# P1.net
KiCad netlist of a schematic drawn in Altium Designer
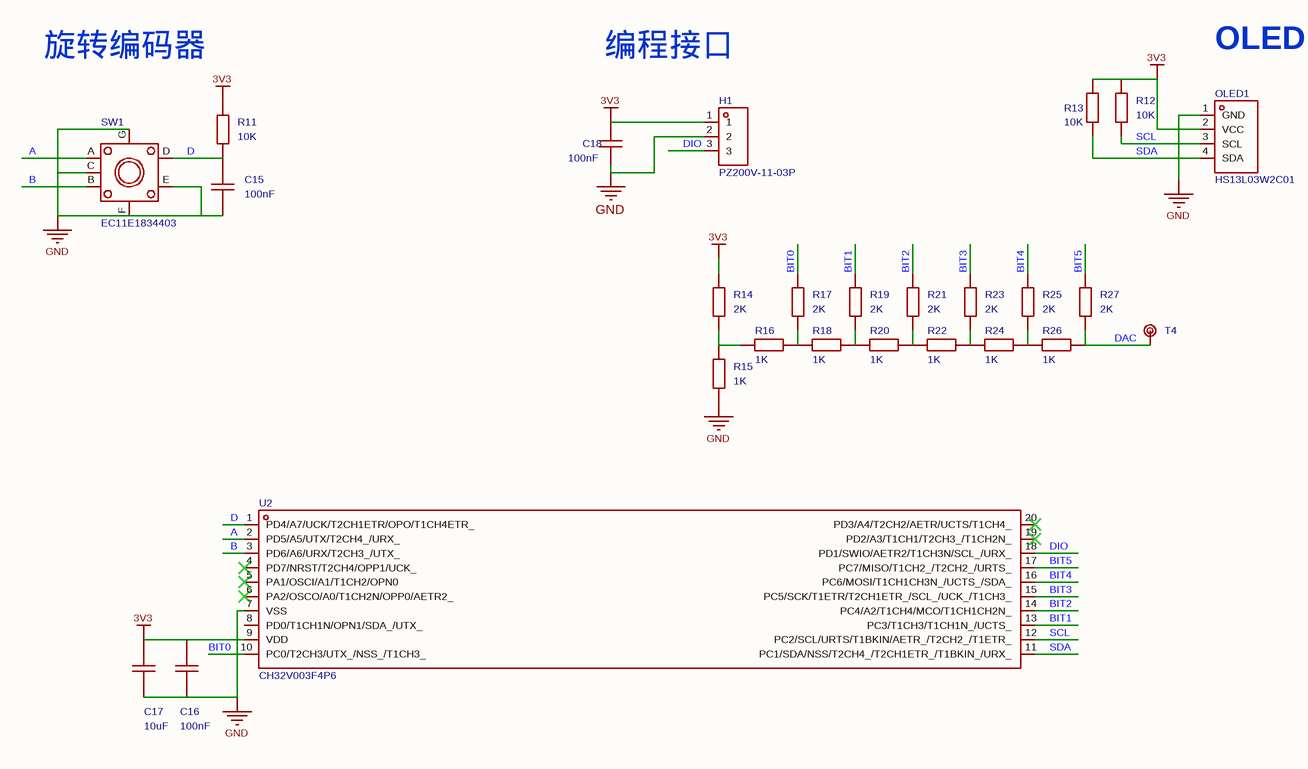
[diagram p0: P1.schdoc]

(export (version "E")
  (design (tool "Eeschema 10.0.6"))
  (components
    (comp (ref "C15")
      (value "100nF")
      (footprint "C0603")
      (libsource (lib "altium-import") (part "root_1_CAP_0603_"))
    )
    (comp (ref "C16")
      (value "100nF")
      (footprint "C0603")
      (libsource (lib "altium-import") (part "root_1_CAP_0603_"))
    )
    (comp (ref "C17")
      (value "10uF")
      (footprint "C0603")
      (libsource (lib "altium-import") (part "root_1_CAP_0603_"))
    )
    (comp (ref "C18")
      (value "100nF")
      (footprint "C0603_1")
      (description "容值:100nF;精度:±10%;额定电压:50V;材质(温度系数):X7R;")
      (fields (field (name "TOLERANCE") "±10%") (field (name "MANUFACTURER") "FH(风华)"))
      (libsource (lib "altium-import") (part "root_1_0603B104K500NT_"))
    )
    (comp (ref "H1")
      (value "PZ200V-11-03P")
      (footprint "HDR-TH_3P-P2.00-V-M")
      (fields (field (name "MANUFACTURER") "XFCN(兴飞)"))
      (libsource (lib "altium-import") (part "root_0_PZ200V-11-03P_"))
    )
    (comp (ref "OLED1")
      (value "HS13L03W2C01")
      (footprint "OLED-TH_L35.4-W33.5_HS13L03W2C01")
      (description "主控芯片:SH1106;接口类型:I2C;尺寸(inch):1.3;")
      (fields (field (name "MANUFACTURER") "HS(汉昇)"))
      (libsource (lib "altium-import") (part "root_0_HS13L03W2C01_"))
    )
    (comp (ref "R11")
      (value "10K")
      (footprint "R0603")
      (libsource (lib "altium-import") (part "root_1_Res_0603_"))
    )
    (comp (ref "R12")
      (value "10K")
      (footprint "R0603")
      (libsource (lib "altium-import") (part "root_1_Res_0603_"))
    )
    (comp (ref "R13")
      (value "10K")
      (footprint "R0603")
      (libsource (lib "altium-import") (part "root_1_Res_0603_"))
    )
    (comp (ref "R14")
      (value "2K")
      (footprint "R0603")
      (libsource (lib "altium-import") (part "root_1_Res_0603_"))
    )
    (comp (ref "R15")
      (value "1K")
      (footprint "R0603")
      (libsource (lib "altium-import") (part "root_1_Res_0603_"))
    )
    (comp (ref "R16")
      (value "1K")
      (footprint "R0603")
      (libsource (lib "altium-import") (part "root_0_Res_0603_"))
    )
    (comp (ref "R17")
      (value "2K")
      (footprint "R0603")
      (libsource (lib "altium-import") (part "root_1_Res_0603_"))
    )
    (comp (ref "R18")
      (value "1K")
      (footprint "R0603")
      (libsource (lib "altium-import") (part "root_0_Res_0603_"))
    )
    (comp (ref "R19")
      (value "2K")
      (footprint "R0603")
      (libsource (lib "altium-import") (part "root_1_Res_0603_"))
    )
    (comp (ref "R20")
      (value "1K")
      (footprint "R0603")
      (libsource (lib "altium-import") (part "root_0_Res_0603_"))
    )
    (comp (ref "R21")
      (value "2K")
      (footprint "R0603")
      (libsource (lib "altium-import") (part "root_1_Res_0603_"))
    )
    (comp (ref "R22")
      (value "1K")
      (footprint "R0603")
      (libsource (lib "altium-import") (part "root_2_Res_0603_"))
    )
    (comp (ref "R23")
      (value "2K")
      (footprint "R0603")
      (libsource (lib "altium-import") (part "root_3_Res_0603_"))
    )
    (comp (ref "R24")
      (value "1K")
      (footprint "R0603")
      (libsource (lib "altium-import") (part "root_0_Res_0603_"))
    )
    (comp (ref "R25")
      (value "2K")
      (footprint "R0603")
      (libsource (lib "altium-import") (part "root_1_Res_0603_"))
    )
    (comp (ref "R26")
      (value "1K")
      (footprint "R0603")
      (libsource (lib "altium-import") (part "root_2_Res_0603_"))
    )
    (comp (ref "R27")
      (value "2K")
      (footprint "R0603")
      (libsource (lib "altium-import") (part "root_1_Res_0603_"))
    )
    (comp (ref "SW1")
      (value "EC11E1834403")
      (footprint "SW-TH_EC11E1820402")
      (fields (field (name "MANUFACTURER") "ALPSALPINE(阿尔卑斯阿尔派)"))
      (libsource (lib "altium-import") (part "root_3_EC11E1834403_"))
    )
    (comp (ref "T4")
      (value "GND")
      (footprint "TP-TH-1.5mm")
      (libsource (lib "altium-import") (part "root_1_测试孔_"))
    )
    (comp (ref "U2")
      (value "CH32V003F4P6")
      (footprint "TSSOP-20_L6.5-W4.4-P0.65-LS6.4-BL")
      (fields (field (name "MANUFACTURER") "WCH(南京沁恒)"))
      (libsource (lib "altium-import") (part "root_0_CH32V003F4P6_"))
    )
  )
  (nets
    (net (code "1") (name "/A") (class "Default")
      (node (ref "SW1") (pin "A") (pinfunction "A_A") (pintype "passive"))
      (node (ref "U2") (pin "2") (pinfunction "PD5/A5/UTX/T2CH4_/URX__2") (pintype "passive"))
    )
    (net (code "2") (name "/B") (class "Default")
      (node (ref "SW1") (pin "B") (pinfunction "B_B") (pintype "passive"))
      (node (ref "U2") (pin "3") (pinfunction "PD6/A6/URX/T2CH3_/UTX__3") (pintype "passive"))
    )
    (net (code "3") (name "/BIT0") (class "Default")
      (node (ref "R17") (pin "2") (pinfunction "2_2") (pintype "passive"))
      (node (ref "U2") (pin "10") (pinfunction "PC0/T2CH3/UTX_/NSS_/T1CH3__10") (pintype "passive"))
    )
    (net (code "4") (name "/BIT1") (class "Default")
      (node (ref "R19") (pin "2") (pinfunction "2_2") (pintype "passive"))
      (node (ref "U2") (pin "13") (pinfunction "PC3/T1CH3/T1CH1N_/UCTS__13") (pintype "passive"))
    )
    (net (code "5") (name "/BIT2") (class "Default")
      (node (ref "R21") (pin "2") (pinfunction "2_2") (pintype "passive"))
      (node (ref "U2") (pin "14") (pinfunction "PC4/A2/T1CH4/MCO/T1CH1CH2N__14") (pintype "passive"))
    )
    (net (code "6") (name "/BIT3") (class "Default")
      (node (ref "R23") (pin "1") (pinfunction "1_1") (pintype "passive"))
      (node (ref "U2") (pin "15") (pinfunction "PC5/SCK/T1ETR/T2CH1ETR_/SCL_/UCK_/T1CH3__15") (pintype "passive"))
    )
    (net (code "7") (name "/BIT4") (class "Default")
      (node (ref "R25") (pin "2") (pinfunction "2_2") (pintype "passive"))
      (node (ref "U2") (pin "16") (pinfunction "PC6/MOSI/T1CH1CH3N_/UCTS_/SDA__16") (pintype "passive"))
    )
    (net (code "8") (name "/BIT5") (class "Default")
      (node (ref "R27") (pin "2") (pinfunction "2_2") (pintype "passive"))
      (node (ref "U2") (pin "17") (pinfunction "PC7/MISO/T1CH2_/T2CH2_/URTS__17") (pintype "passive"))
    )
    (net (code "9") (name "/D") (class "Default")
      (node (ref "C15") (pin "2") (pinfunction "2_2") (pintype "passive"))
      (node (ref "R11") (pin "1") (pinfunction "1_1") (pintype "passive"))
      (node (ref "SW1") (pin "D") (pinfunction "D_D") (pintype "passive"))
      (node (ref "U2") (pin "1") (pinfunction "PD4/A7/UCK/T2CH1ETR/OPO/T1CH4ETR__1") (pintype "passive"))
    )
    (net (code "10") (name "/DAC") (class "Default")
      (node (ref "R26") (pin "1") (pinfunction "1_1") (pintype "passive"))
      (node (ref "R27") (pin "1") (pinfunction "1_1") (pintype "passive"))
      (node (ref "T4") (pin "1") (pinfunction "1_1") (pintype "passive"))
    )
    (net (code "11") (name "/DIO") (class "Default")
      (node (ref "H1") (pin "3") (pinfunction "3_3") (pintype "passive"))
      (node (ref "U2") (pin "18") (pinfunction "PD1/SWIO/AETR2/T1CH3N/SCL_/URX__18") (pintype "passive"))
    )
    (net (code "12") (name "/SCL") (class "Default")
      (node (ref "OLED1") (pin "3") (pinfunction "SCL_3") (pintype "passive"))
      (node (ref "R12") (pin "1") (pinfunction "1_1") (pintype "passive"))
      (node (ref "U2") (pin "12") (pinfunction "PC2/SCL/URTS/T1BKIN/AETR_/T2CH2_/T1ETR__12") (pintype "passive"))
    )
    (net (code "13") (name "/SDA") (class "Default")
      (node (ref "OLED1") (pin "4") (pinfunction "SDA_4") (pintype "passive"))
      (node (ref "R13") (pin "1") (pinfunction "1_1") (pintype "passive"))
      (node (ref "U2") (pin "11") (pinfunction "PC1/SDA/NSS/T2CH4_/T2CH1ETR_/T1BKIN_/URX__11") (pintype "passive"))
    )
    (net (code "14") (name "3V3") (class "Default")
      (node (ref "C16") (pin "2") (pinfunction "2_2") (pintype "passive"))
      (node (ref "C17") (pin "2") (pinfunction "2_2") (pintype "passive"))
      (node (ref "C18") (pin "2") (pinfunction "2_2") (pintype "passive"))
      (node (ref "H1") (pin "1") (pinfunction "1_1") (pintype "passive"))
      (node (ref "OLED1") (pin "2") (pinfunction "VCC_2") (pintype "passive"))
      (node (ref "R11") (pin "2") (pinfunction "2_2") (pintype "passive"))
      (node (ref "R12") (pin "2") (pinfunction "2_2") (pintype "passive"))
      (node (ref "R13") (pin "2") (pinfunction "2_2") (pintype "passive"))
      (node (ref "R14") (pin "2") (pinfunction "2_2") (pintype "passive"))
      (node (ref "U2") (pin "9") (pinfunction "VDD_9") (pintype "passive"))
    )
    (net (code "15") (name "GND") (class "Default")
      (node (ref "C15") (pin "1") (pinfunction "1_1") (pintype "passive"))
      (node (ref "C16") (pin "1") (pinfunction "1_1") (pintype "passive"))
      (node (ref "C17") (pin "1") (pinfunction "1_1") (pintype "passive"))
      (node (ref "C18") (pin "1") (pinfunction "1_1") (pintype "passive"))
      (node (ref "H1") (pin "2") (pinfunction "2_2") (pintype "passive"))
      (node (ref "OLED1") (pin "1") (pinfunction "GND_1") (pintype "passive"))
      (node (ref "R15") (pin "1") (pinfunction "1_1") (pintype "passive"))
      (node (ref "SW1") (pin "C") (pinfunction "C_C") (pintype "passive"))
      (node (ref "SW1") (pin "E") (pinfunction "E_E") (pintype "passive"))
      (node (ref "SW1") (pin "F") (pinfunction "F_F") (pintype "passive"))
      (node (ref "SW1") (pin "G") (pinfunction "G_G") (pintype "passive"))
      (node (ref "U2") (pin "7") (pinfunction "VSS_7") (pintype "passive"))
    )
    (net (code "16") (name "Net-(R14-Pad1)") (class "Default")
      (node (ref "R14") (pin "1") (pinfunction "1_1") (pintype "passive"))
      (node (ref "R15") (pin "2") (pinfunction "2_2") (pintype "passive"))
      (node (ref "R16") (pin "1") (pinfunction "1_1") (pintype "passive"))
    )
    (net (code "17") (name "Net-(R16-Pad2)") (class "Default")
      (node (ref "R16") (pin "2") (pinfunction "2_2") (pintype "passive"))
      (node (ref "R17") (pin "1") (pinfunction "1_1") (pintype "passive"))
      (node (ref "R18") (pin "1") (pinfunction "1_1") (pintype "passive"))
    )
    (net (code "18") (name "Net-(R18-Pad2)") (class "Default")
      (node (ref "R18") (pin "2") (pinfunction "2_2") (pintype "passive"))
      (node (ref "R19") (pin "1") (pinfunction "1_1") (pintype "passive"))
      (node (ref "R20") (pin "1") (pinfunction "1_1") (pintype "passive"))
    )
    (net (code "19") (name "Net-(R20-Pad2)") (class "Default")
      (node (ref "R20") (pin "2") (pinfunction "2_2") (pintype "passive"))
      (node (ref "R21") (pin "1") (pinfunction "1_1") (pintype "passive"))
      (node (ref "R22") (pin "2") (pinfunction "2_2") (pintype "passive"))
    )
    (net (code "20") (name "Net-(R22-Pad1)") (class "Default")
      (node (ref "R22") (pin "1") (pinfunction "1_1") (pintype "passive"))
      (node (ref "R23") (pin "2") (pinfunction "2_2") (pintype "passive"))
      (node (ref "R24") (pin "1") (pinfunction "1_1") (pintype "passive"))
    )
    (net (code "21") (name "Net-(R24-Pad2)") (class "Default")
      (node (ref "R24") (pin "2") (pinfunction "2_2") (pintype "passive"))
      (node (ref "R25") (pin "1") (pinfunction "1_1") (pintype "passive"))
      (node (ref "R26") (pin "2") (pinfunction "2_2") (pintype "passive"))
    )
    (net (code "22") (name "unconnected-(U2-PA1{slash}OSCI{slash}A1{slash}T1CH2{slash}OPN0-Pad5)") (class "Default")
      (node (ref "U2") (pin "5") (pinfunction "PA1/OSCI/A1/T1CH2/OPN0_5") (pintype "passive+no_connect"))
    )
    (net (code "23") (name "unconnected-(U2-PA2{slash}OSCO{slash}A0{slash}T1CH2N{slash}OPP0{slash}AETR2_-Pad6)") (class "Default")
      (node (ref "U2") (pin "6") (pinfunction "PA2/OSCO/A0/T1CH2N/OPP0/AETR2__6") (pintype "passive+no_connect"))
    )
    (net (code "24") (name "unconnected-(U2-PD0{slash}T1CH1N{slash}OPN1{slash}SDA_{slash}UTX_-Pad8)") (class "Default")
      (node (ref "U2") (pin "8") (pinfunction "PD0/T1CH1N/OPN1/SDA_/UTX__8") (pintype "passive"))
    )
    (net (code "25") (name "unconnected-(U2-PD2{slash}A3{slash}T1CH1{slash}T2CH3_{slash}T1CH2N_-Pad19)") (class "Default")
      (node (ref "U2") (pin "19") (pinfunction "PD2/A3/T1CH1/T2CH3_/T1CH2N__19") (pintype "passive+no_connect"))
    )
    (net (code "26") (name "unconnected-(U2-PD3{slash}A4{slash}T2CH2{slash}AETR{slash}UCTS{slash}T1CH4_-Pad20)") (class "Default")
      (node (ref "U2") (pin "20") (pinfunction "PD3/A4/T2CH2/AETR/UCTS/T1CH4__20") (pintype "passive+no_connect"))
    )
    (net (code "27") (name "unconnected-(U2-PD7{slash}NRST{slash}T2CH4{slash}OPP1{slash}UCK_-Pad4)") (class "Default")
      (node (ref "U2") (pin "4") (pinfunction "PD7/NRST/T2CH4/OPP1/UCK__4") (pintype "passive+no_connect"))
    )
  )
)
